# B141A.net
KiCad netlist of a schematic drawn in EAGLE
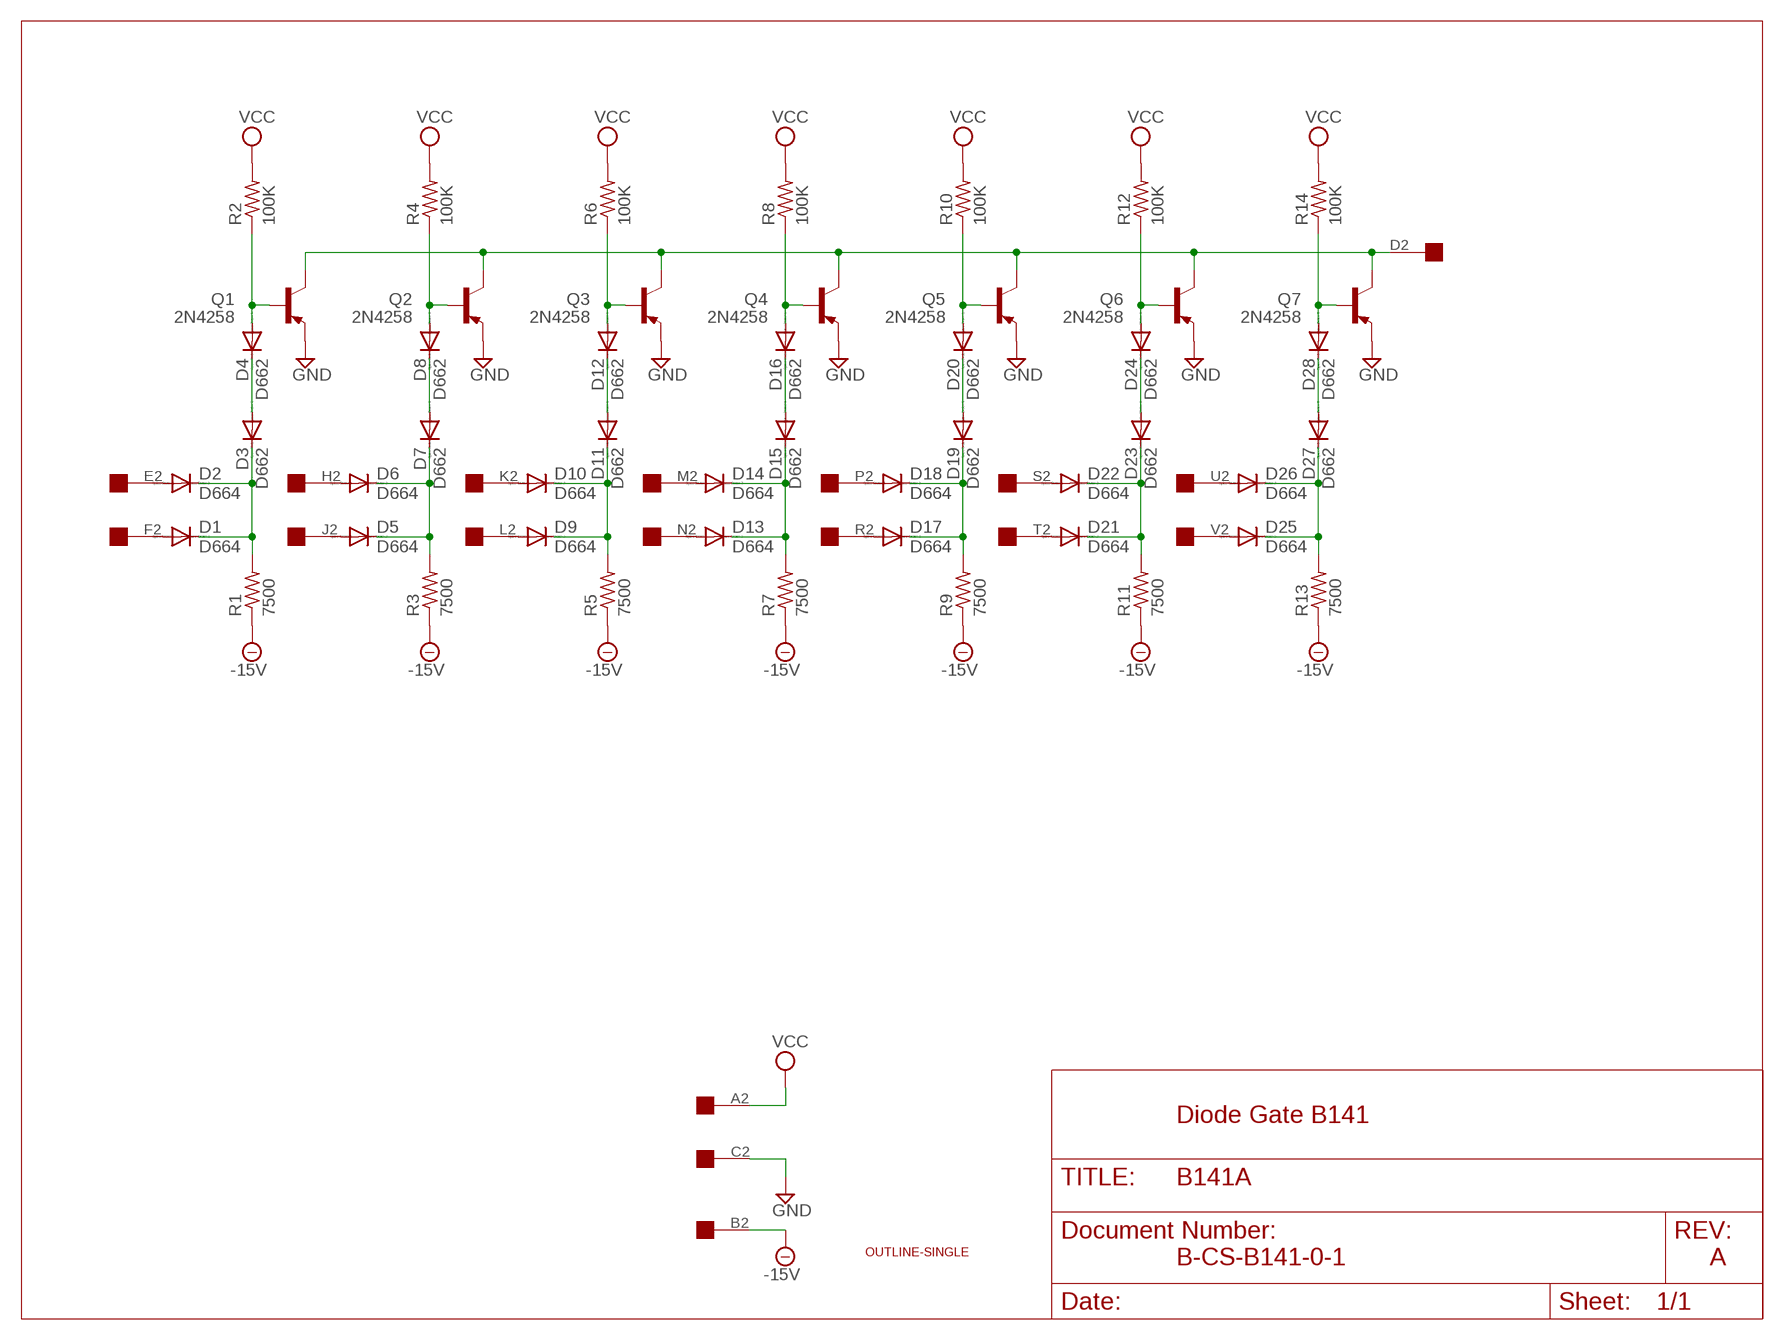
[diagram p0: schematic, sheet 1]

(export (version "E")
  (design (tool "Eeschema 10.0.6"))
  (components
    (comp (ref "D1")
      (value "D664")
      (footprint "eagle-import:DO35-10")
      (libsource (lib "eagle-import") (part "DIODE-DO35-10"))
    )
    (comp (ref "D2")
      (value "D664")
      (footprint "eagle-import:DO35-10")
      (libsource (lib "eagle-import") (part "DIODE-DO35-10"))
    )
    (comp (ref "D3")
      (value "D662")
      (footprint "eagle-import:DO35-10")
      (libsource (lib "eagle-import") (part "DIODE-DO35-10"))
    )
    (comp (ref "D4")
      (value "D662")
      (footprint "eagle-import:DO35-10")
      (libsource (lib "eagle-import") (part "DIODE-DO35-10"))
    )
    (comp (ref "D5")
      (value "D664")
      (footprint "eagle-import:DO35-10")
      (libsource (lib "eagle-import") (part "DIODE-DO35-10"))
    )
    (comp (ref "D6")
      (value "D664")
      (footprint "eagle-import:DO35-10")
      (libsource (lib "eagle-import") (part "DIODE-DO35-10"))
    )
    (comp (ref "D7")
      (value "D662")
      (footprint "eagle-import:DO35-10")
      (libsource (lib "eagle-import") (part "DIODE-DO35-10"))
    )
    (comp (ref "D8")
      (value "D662")
      (footprint "eagle-import:DO35-10")
      (libsource (lib "eagle-import") (part "DIODE-DO35-10"))
    )
    (comp (ref "D9")
      (value "D664")
      (footprint "eagle-import:DO35-10")
      (libsource (lib "eagle-import") (part "DIODE-DO35-10"))
    )
    (comp (ref "D10")
      (value "D664")
      (footprint "eagle-import:DO35-10")
      (libsource (lib "eagle-import") (part "DIODE-DO35-10"))
    )
    (comp (ref "D11")
      (value "D662")
      (footprint "eagle-import:DO35-10")
      (libsource (lib "eagle-import") (part "DIODE-DO35-10"))
    )
    (comp (ref "D12")
      (value "D662")
      (footprint "eagle-import:DO35-10")
      (libsource (lib "eagle-import") (part "DIODE-DO35-10"))
    )
    (comp (ref "D13")
      (value "D664")
      (footprint "eagle-import:DO35-10")
      (libsource (lib "eagle-import") (part "DIODE-DO35-10"))
    )
    (comp (ref "D14")
      (value "D664")
      (footprint "eagle-import:DO35-10")
      (libsource (lib "eagle-import") (part "DIODE-DO35-10"))
    )
    (comp (ref "D15")
      (value "D662")
      (footprint "eagle-import:DO35-10")
      (libsource (lib "eagle-import") (part "DIODE-DO35-10"))
    )
    (comp (ref "D16")
      (value "D662")
      (footprint "eagle-import:DO35-10")
      (libsource (lib "eagle-import") (part "DIODE-DO35-10"))
    )
    (comp (ref "D17")
      (value "D664")
      (footprint "eagle-import:DO35-10")
      (libsource (lib "eagle-import") (part "DIODE-DO35-10"))
    )
    (comp (ref "D18")
      (value "D664")
      (footprint "eagle-import:DO35-10")
      (libsource (lib "eagle-import") (part "DIODE-DO35-10"))
    )
    (comp (ref "D19")
      (value "D662")
      (footprint "eagle-import:DO35-10")
      (libsource (lib "eagle-import") (part "DIODE-DO35-10"))
    )
    (comp (ref "D20")
      (value "D662")
      (footprint "eagle-import:DO35-10")
      (libsource (lib "eagle-import") (part "DIODE-DO35-10"))
    )
    (comp (ref "D21")
      (value "D664")
      (footprint "eagle-import:DO35-10")
      (libsource (lib "eagle-import") (part "DIODE-DO35-10"))
    )
    (comp (ref "D22")
      (value "D664")
      (footprint "eagle-import:DO35-10")
      (libsource (lib "eagle-import") (part "DIODE-DO35-10"))
    )
    (comp (ref "D23")
      (value "D662")
      (footprint "eagle-import:DO35-10")
      (libsource (lib "eagle-import") (part "DIODE-DO35-10"))
    )
    (comp (ref "D24")
      (value "D662")
      (footprint "eagle-import:DO35-10")
      (libsource (lib "eagle-import") (part "DIODE-DO35-10"))
    )
    (comp (ref "D25")
      (value "D664")
      (footprint "eagle-import:DO35-10")
      (libsource (lib "eagle-import") (part "DIODE-DO35-10"))
    )
    (comp (ref "D26")
      (value "D664")
      (footprint "eagle-import:DO35-10")
      (libsource (lib "eagle-import") (part "DIODE-DO35-10"))
    )
    (comp (ref "D27")
      (value "D662")
      (footprint "eagle-import:DO35-10")
      (libsource (lib "eagle-import") (part "DIODE-DO35-10"))
    )
    (comp (ref "D28")
      (value "D662")
      (footprint "eagle-import:DO35-10")
      (libsource (lib "eagle-import") (part "DIODE-DO35-10"))
    )
    (comp (ref "Q1")
      (value "2N4258")
      (footprint "eagle-import:TO5")
      (libsource (lib "eagle-import") (part "-PNP-TO5"))
    )
    (comp (ref "Q2")
      (value "2N4258")
      (footprint "eagle-import:TO5")
      (libsource (lib "eagle-import") (part "-PNP-TO5"))
    )
    (comp (ref "Q3")
      (value "2N4258")
      (footprint "eagle-import:TO5")
      (libsource (lib "eagle-import") (part "-PNP-TO5"))
    )
    (comp (ref "Q4")
      (value "2N4258")
      (footprint "eagle-import:TO5")
      (libsource (lib "eagle-import") (part "-PNP-TO5"))
    )
    (comp (ref "Q5")
      (value "2N4258")
      (footprint "eagle-import:TO5")
      (libsource (lib "eagle-import") (part "-PNP-TO5"))
    )
    (comp (ref "Q6")
      (value "2N4258")
      (footprint "eagle-import:TO5")
      (libsource (lib "eagle-import") (part "-PNP-TO5"))
    )
    (comp (ref "Q7")
      (value "2N4258")
      (footprint "eagle-import:TO5")
      (libsource (lib "eagle-import") (part "-PNP-TO5"))
    )
    (comp (ref "R1")
      (value "7500")
      (footprint "eagle-import:0207_10")
      (libsource (lib "eagle-import") (part "R-US_0207/10"))
    )
    (comp (ref "R2")
      (value "100K")
      (footprint "eagle-import:0207_10")
      (libsource (lib "eagle-import") (part "R-US_0207/10"))
    )
    (comp (ref "R3")
      (value "7500")
      (footprint "eagle-import:0207_10")
      (libsource (lib "eagle-import") (part "R-US_0207/10"))
    )
    (comp (ref "R4")
      (value "100K")
      (footprint "eagle-import:0207_10")
      (libsource (lib "eagle-import") (part "R-US_0207/10"))
    )
    (comp (ref "R5")
      (value "7500")
      (footprint "eagle-import:0207_10")
      (libsource (lib "eagle-import") (part "R-US_0207/10"))
    )
    (comp (ref "R6")
      (value "100K")
      (footprint "eagle-import:0207_10")
      (libsource (lib "eagle-import") (part "R-US_0207/10"))
    )
    (comp (ref "R7")
      (value "7500")
      (footprint "eagle-import:0207_10")
      (libsource (lib "eagle-import") (part "R-US_0207/10"))
    )
    (comp (ref "R8")
      (value "100K")
      (footprint "eagle-import:0207_10")
      (libsource (lib "eagle-import") (part "R-US_0207/10"))
    )
    (comp (ref "R9")
      (value "7500")
      (footprint "eagle-import:0207_10")
      (libsource (lib "eagle-import") (part "R-US_0207/10"))
    )
    (comp (ref "R10")
      (value "100K")
      (footprint "eagle-import:0207_10")
      (libsource (lib "eagle-import") (part "R-US_0207/10"))
    )
    (comp (ref "R11")
      (value "7500")
      (footprint "eagle-import:0207_10")
      (libsource (lib "eagle-import") (part "R-US_0207/10"))
    )
    (comp (ref "R12")
      (value "100K")
      (footprint "eagle-import:0207_10")
      (libsource (lib "eagle-import") (part "R-US_0207/10"))
    )
    (comp (ref "R13")
      (value "7500")
      (footprint "eagle-import:0207_10")
      (libsource (lib "eagle-import") (part "R-US_0207/10"))
    )
    (comp (ref "R14")
      (value "100K")
      (footprint "eagle-import:0207_10")
      (libsource (lib "eagle-import") (part "R-US_0207/10"))
    )
    (comp (ref "U$1")
      (value "OUTLINE-SINGLE")
      (footprint "eagle-import:SINGLE")
      (libsource (lib "eagle-import") (part "OUTLINE-SINGLE"))
    )
    (comp (ref "U$2")
      (value "EDGE-1")
      (footprint "eagle-import:EDGE-CON1")
      (libsource (lib "eagle-import") (part "EDGE-1"))
    )
  )
  (nets
    (net (code "1") (name "-15V") (class "Default")
      (node (ref "R1") (pin "1") (pinfunction "1_1") (pintype "passive"))
      (node (ref "R11") (pin "1") (pinfunction "1_1") (pintype "passive"))
      (node (ref "R13") (pin "1") (pinfunction "1_1") (pintype "passive"))
      (node (ref "R3") (pin "1") (pinfunction "1_1") (pintype "passive"))
      (node (ref "R5") (pin "1") (pinfunction "1_1") (pintype "passive"))
      (node (ref "R7") (pin "1") (pinfunction "1_1") (pintype "passive"))
      (node (ref "R9") (pin "1") (pinfunction "1_1") (pintype "passive"))
      (node (ref "U$2") (pin "B2") (pinfunction "1_B2") (pintype "bidirectional"))
    )
    (net (code "2") (name "GND") (class "Default")
      (node (ref "Q1") (pin "1") (pinfunction "E_1") (pintype "passive"))
      (node (ref "Q2") (pin "1") (pinfunction "E_1") (pintype "passive"))
      (node (ref "Q3") (pin "1") (pinfunction "E_1") (pintype "passive"))
      (node (ref "Q4") (pin "1") (pinfunction "E_1") (pintype "passive"))
      (node (ref "Q5") (pin "1") (pinfunction "E_1") (pintype "passive"))
      (node (ref "Q6") (pin "1") (pinfunction "E_1") (pintype "passive"))
      (node (ref "Q7") (pin "1") (pinfunction "E_1") (pintype "passive"))
      (node (ref "U$2") (pin "C2") (pinfunction "1_C2") (pintype "bidirectional"))
    )
    (net (code "3") (name "Net-(D1-PadC)") (class "Default")
      (node (ref "D1") (pin "C") (pinfunction "C_C") (pintype "passive"))
      (node (ref "D2") (pin "C") (pinfunction "C_C") (pintype "passive"))
      (node (ref "D3") (pin "C") (pinfunction "C_C") (pintype "passive"))
      (node (ref "R1") (pin "2") (pinfunction "2_2") (pintype "passive"))
    )
    (net (code "4") (name "Net-(D3-PadA)") (class "Default")
      (node (ref "D3") (pin "A") (pinfunction "A_A") (pintype "passive"))
      (node (ref "D4") (pin "C") (pinfunction "C_C") (pintype "passive"))
    )
    (net (code "5") (name "Net-(D5-PadC)") (class "Default")
      (node (ref "D5") (pin "C") (pinfunction "C_C") (pintype "passive"))
      (node (ref "D6") (pin "C") (pinfunction "C_C") (pintype "passive"))
      (node (ref "D7") (pin "C") (pinfunction "C_C") (pintype "passive"))
      (node (ref "R3") (pin "2") (pinfunction "2_2") (pintype "passive"))
    )
    (net (code "6") (name "Net-(D7-PadA)") (class "Default")
      (node (ref "D7") (pin "A") (pinfunction "A_A") (pintype "passive"))
      (node (ref "D8") (pin "C") (pinfunction "C_C") (pintype "passive"))
    )
    (net (code "7") (name "Net-(D10-PadC)") (class "Default")
      (node (ref "D10") (pin "C") (pinfunction "C_C") (pintype "passive"))
      (node (ref "D11") (pin "C") (pinfunction "C_C") (pintype "passive"))
      (node (ref "D9") (pin "C") (pinfunction "C_C") (pintype "passive"))
      (node (ref "R5") (pin "2") (pinfunction "2_2") (pintype "passive"))
    )
    (net (code "8") (name "Net-(D11-PadA)") (class "Default")
      (node (ref "D11") (pin "A") (pinfunction "A_A") (pintype "passive"))
      (node (ref "D12") (pin "C") (pinfunction "C_C") (pintype "passive"))
    )
    (net (code "9") (name "Net-(D13-PadC)") (class "Default")
      (node (ref "D13") (pin "C") (pinfunction "C_C") (pintype "passive"))
      (node (ref "D14") (pin "C") (pinfunction "C_C") (pintype "passive"))
      (node (ref "D15") (pin "C") (pinfunction "C_C") (pintype "passive"))
      (node (ref "R7") (pin "2") (pinfunction "2_2") (pintype "passive"))
    )
    (net (code "10") (name "Net-(D15-PadA)") (class "Default")
      (node (ref "D15") (pin "A") (pinfunction "A_A") (pintype "passive"))
      (node (ref "D16") (pin "C") (pinfunction "C_C") (pintype "passive"))
    )
    (net (code "11") (name "Net-(D17-PadC)") (class "Default")
      (node (ref "D17") (pin "C") (pinfunction "C_C") (pintype "passive"))
      (node (ref "D18") (pin "C") (pinfunction "C_C") (pintype "passive"))
      (node (ref "D19") (pin "C") (pinfunction "C_C") (pintype "passive"))
      (node (ref "R9") (pin "2") (pinfunction "2_2") (pintype "passive"))
    )
    (net (code "12") (name "Net-(D19-PadA)") (class "Default")
      (node (ref "D19") (pin "A") (pinfunction "A_A") (pintype "passive"))
      (node (ref "D20") (pin "C") (pinfunction "C_C") (pintype "passive"))
    )
    (net (code "13") (name "Net-(D21-PadC)") (class "Default")
      (node (ref "D21") (pin "C") (pinfunction "C_C") (pintype "passive"))
      (node (ref "D22") (pin "C") (pinfunction "C_C") (pintype "passive"))
      (node (ref "D23") (pin "C") (pinfunction "C_C") (pintype "passive"))
      (node (ref "R11") (pin "2") (pinfunction "2_2") (pintype "passive"))
    )
    (net (code "14") (name "Net-(D23-PadA)") (class "Default")
      (node (ref "D23") (pin "A") (pinfunction "A_A") (pintype "passive"))
      (node (ref "D24") (pin "C") (pinfunction "C_C") (pintype "passive"))
    )
    (net (code "15") (name "Net-(D25-PadC)") (class "Default")
      (node (ref "D25") (pin "C") (pinfunction "C_C") (pintype "passive"))
      (node (ref "D26") (pin "C") (pinfunction "C_C") (pintype "passive"))
      (node (ref "D27") (pin "C") (pinfunction "C_C") (pintype "passive"))
      (node (ref "R13") (pin "2") (pinfunction "2_2") (pintype "passive"))
    )
    (net (code "16") (name "Net-(D27-PadA)") (class "Default")
      (node (ref "D27") (pin "A") (pinfunction "A_A") (pintype "passive"))
      (node (ref "D28") (pin "C") (pinfunction "C_C") (pintype "passive"))
    )
    (net (code "17") (name "Net-(Q1-B)") (class "Default")
      (node (ref "D4") (pin "A") (pinfunction "A_A") (pintype "passive"))
      (node (ref "Q1") (pin "2") (pinfunction "B_2") (pintype "passive"))
      (node (ref "R2") (pin "1") (pinfunction "1_1") (pintype "passive"))
    )
    (net (code "18") (name "Net-(Q1-C)") (class "Default")
      (node (ref "Q1") (pin "3") (pinfunction "C_3") (pintype "passive"))
      (node (ref "Q2") (pin "3") (pinfunction "C_3") (pintype "passive"))
      (node (ref "Q3") (pin "3") (pinfunction "C_3") (pintype "passive"))
      (node (ref "Q4") (pin "3") (pinfunction "C_3") (pintype "passive"))
      (node (ref "Q5") (pin "3") (pinfunction "C_3") (pintype "passive"))
      (node (ref "Q6") (pin "3") (pinfunction "C_3") (pintype "passive"))
      (node (ref "Q7") (pin "3") (pinfunction "C_3") (pintype "passive"))
      (node (ref "U$2") (pin "D2") (pinfunction "1_D2") (pintype "bidirectional"))
    )
    (net (code "19") (name "Net-(Q2-B)") (class "Default")
      (node (ref "D8") (pin "A") (pinfunction "A_A") (pintype "passive"))
      (node (ref "Q2") (pin "2") (pinfunction "B_2") (pintype "passive"))
      (node (ref "R4") (pin "1") (pinfunction "1_1") (pintype "passive"))
    )
    (net (code "20") (name "Net-(Q3-B)") (class "Default")
      (node (ref "D12") (pin "A") (pinfunction "A_A") (pintype "passive"))
      (node (ref "Q3") (pin "2") (pinfunction "B_2") (pintype "passive"))
      (node (ref "R6") (pin "1") (pinfunction "1_1") (pintype "passive"))
    )
    (net (code "21") (name "Net-(Q4-B)") (class "Default")
      (node (ref "D16") (pin "A") (pinfunction "A_A") (pintype "passive"))
      (node (ref "Q4") (pin "2") (pinfunction "B_2") (pintype "passive"))
      (node (ref "R8") (pin "1") (pinfunction "1_1") (pintype "passive"))
    )
    (net (code "22") (name "Net-(Q5-B)") (class "Default")
      (node (ref "D20") (pin "A") (pinfunction "A_A") (pintype "passive"))
      (node (ref "Q5") (pin "2") (pinfunction "B_2") (pintype "passive"))
      (node (ref "R10") (pin "1") (pinfunction "1_1") (pintype "passive"))
    )
    (net (code "23") (name "Net-(Q6-B)") (class "Default")
      (node (ref "D24") (pin "A") (pinfunction "A_A") (pintype "passive"))
      (node (ref "Q6") (pin "2") (pinfunction "B_2") (pintype "passive"))
      (node (ref "R12") (pin "1") (pinfunction "1_1") (pintype "passive"))
    )
    (net (code "24") (name "Net-(Q7-B)") (class "Default")
      (node (ref "D28") (pin "A") (pinfunction "A_A") (pintype "passive"))
      (node (ref "Q7") (pin "2") (pinfunction "B_2") (pintype "passive"))
      (node (ref "R14") (pin "1") (pinfunction "1_1") (pintype "passive"))
    )
    (net (code "25") (name "Net-(U$2E-1)") (class "Default")
      (node (ref "D2") (pin "A") (pinfunction "A_A") (pintype "passive"))
      (node (ref "U$2") (pin "E2") (pinfunction "1_E2") (pintype "bidirectional"))
    )
    (net (code "26") (name "Net-(U$2F-1)") (class "Default")
      (node (ref "D1") (pin "A") (pinfunction "A_A") (pintype "passive"))
      (node (ref "U$2") (pin "F2") (pinfunction "1_F2") (pintype "bidirectional"))
    )
    (net (code "27") (name "Net-(U$2G-1)") (class "Default")
      (node (ref "D6") (pin "A") (pinfunction "A_A") (pintype "passive"))
      (node (ref "U$2") (pin "H2") (pinfunction "1_H2") (pintype "bidirectional"))
    )
    (net (code "28") (name "Net-(U$2H-1)") (class "Default")
      (node (ref "D5") (pin "A") (pinfunction "A_A") (pintype "passive"))
      (node (ref "U$2") (pin "J2") (pinfunction "1_J2") (pintype "bidirectional"))
    )
    (net (code "29") (name "Net-(U$2I-1)") (class "Default")
      (node (ref "D10") (pin "A") (pinfunction "A_A") (pintype "passive"))
      (node (ref "U$2") (pin "K2") (pinfunction "1_K2") (pintype "bidirectional"))
    )
    (net (code "30") (name "Net-(U$2J-1)") (class "Default")
      (node (ref "D9") (pin "A") (pinfunction "A_A") (pintype "passive"))
      (node (ref "U$2") (pin "L2") (pinfunction "1_L2") (pintype "bidirectional"))
    )
    (net (code "31") (name "Net-(U$2K-1)") (class "Default")
      (node (ref "D14") (pin "A") (pinfunction "A_A") (pintype "passive"))
      (node (ref "U$2") (pin "M2") (pinfunction "1_M2") (pintype "bidirectional"))
    )
    (net (code "32") (name "Net-(U$2L-1)") (class "Default")
      (node (ref "D13") (pin "A") (pinfunction "A_A") (pintype "passive"))
      (node (ref "U$2") (pin "N2") (pinfunction "1_N2") (pintype "bidirectional"))
    )
    (net (code "33") (name "Net-(U$2M-1)") (class "Default")
      (node (ref "D18") (pin "A") (pinfunction "A_A") (pintype "passive"))
      (node (ref "U$2") (pin "P2") (pinfunction "1_P2") (pintype "bidirectional"))
    )
    (net (code "34") (name "Net-(U$2N-1)") (class "Default")
      (node (ref "D17") (pin "A") (pinfunction "A_A") (pintype "passive"))
      (node (ref "U$2") (pin "R2") (pinfunction "1_R2") (pintype "bidirectional"))
    )
    (net (code "35") (name "Net-(U$2O-1)") (class "Default")
      (node (ref "D22") (pin "A") (pinfunction "A_A") (pintype "passive"))
      (node (ref "U$2") (pin "S2") (pinfunction "1_S2") (pintype "bidirectional"))
    )
    (net (code "36") (name "Net-(U$2P-1)") (class "Default")
      (node (ref "D21") (pin "A") (pinfunction "A_A") (pintype "passive"))
      (node (ref "U$2") (pin "T2") (pinfunction "1_T2") (pintype "bidirectional"))
    )
    (net (code "37") (name "Net-(U$2Q-1)") (class "Default")
      (node (ref "D26") (pin "A") (pinfunction "A_A") (pintype "passive"))
      (node (ref "U$2") (pin "U2") (pinfunction "1_U2") (pintype "bidirectional"))
    )
    (net (code "38") (name "Net-(U$2R-1)") (class "Default")
      (node (ref "D25") (pin "A") (pinfunction "A_A") (pintype "passive"))
      (node (ref "U$2") (pin "V2") (pinfunction "1_V2") (pintype "bidirectional"))
    )
    (net (code "39") (name "VCC") (class "Default")
      (node (ref "R10") (pin "2") (pinfunction "2_2") (pintype "passive"))
      (node (ref "R12") (pin "2") (pinfunction "2_2") (pintype "passive"))
      (node (ref "R14") (pin "2") (pinfunction "2_2") (pintype "passive"))
      (node (ref "R2") (pin "2") (pinfunction "2_2") (pintype "passive"))
      (node (ref "R4") (pin "2") (pinfunction "2_2") (pintype "passive"))
      (node (ref "R6") (pin "2") (pinfunction "2_2") (pintype "passive"))
      (node (ref "R8") (pin "2") (pinfunction "2_2") (pintype "passive"))
      (node (ref "U$2") (pin "A2") (pinfunction "1_A2") (pintype "bidirectional"))
    )
  )
)
